# 01_digital_back_end.net
KiCad netlist of a schematic drawn in Altium Designer
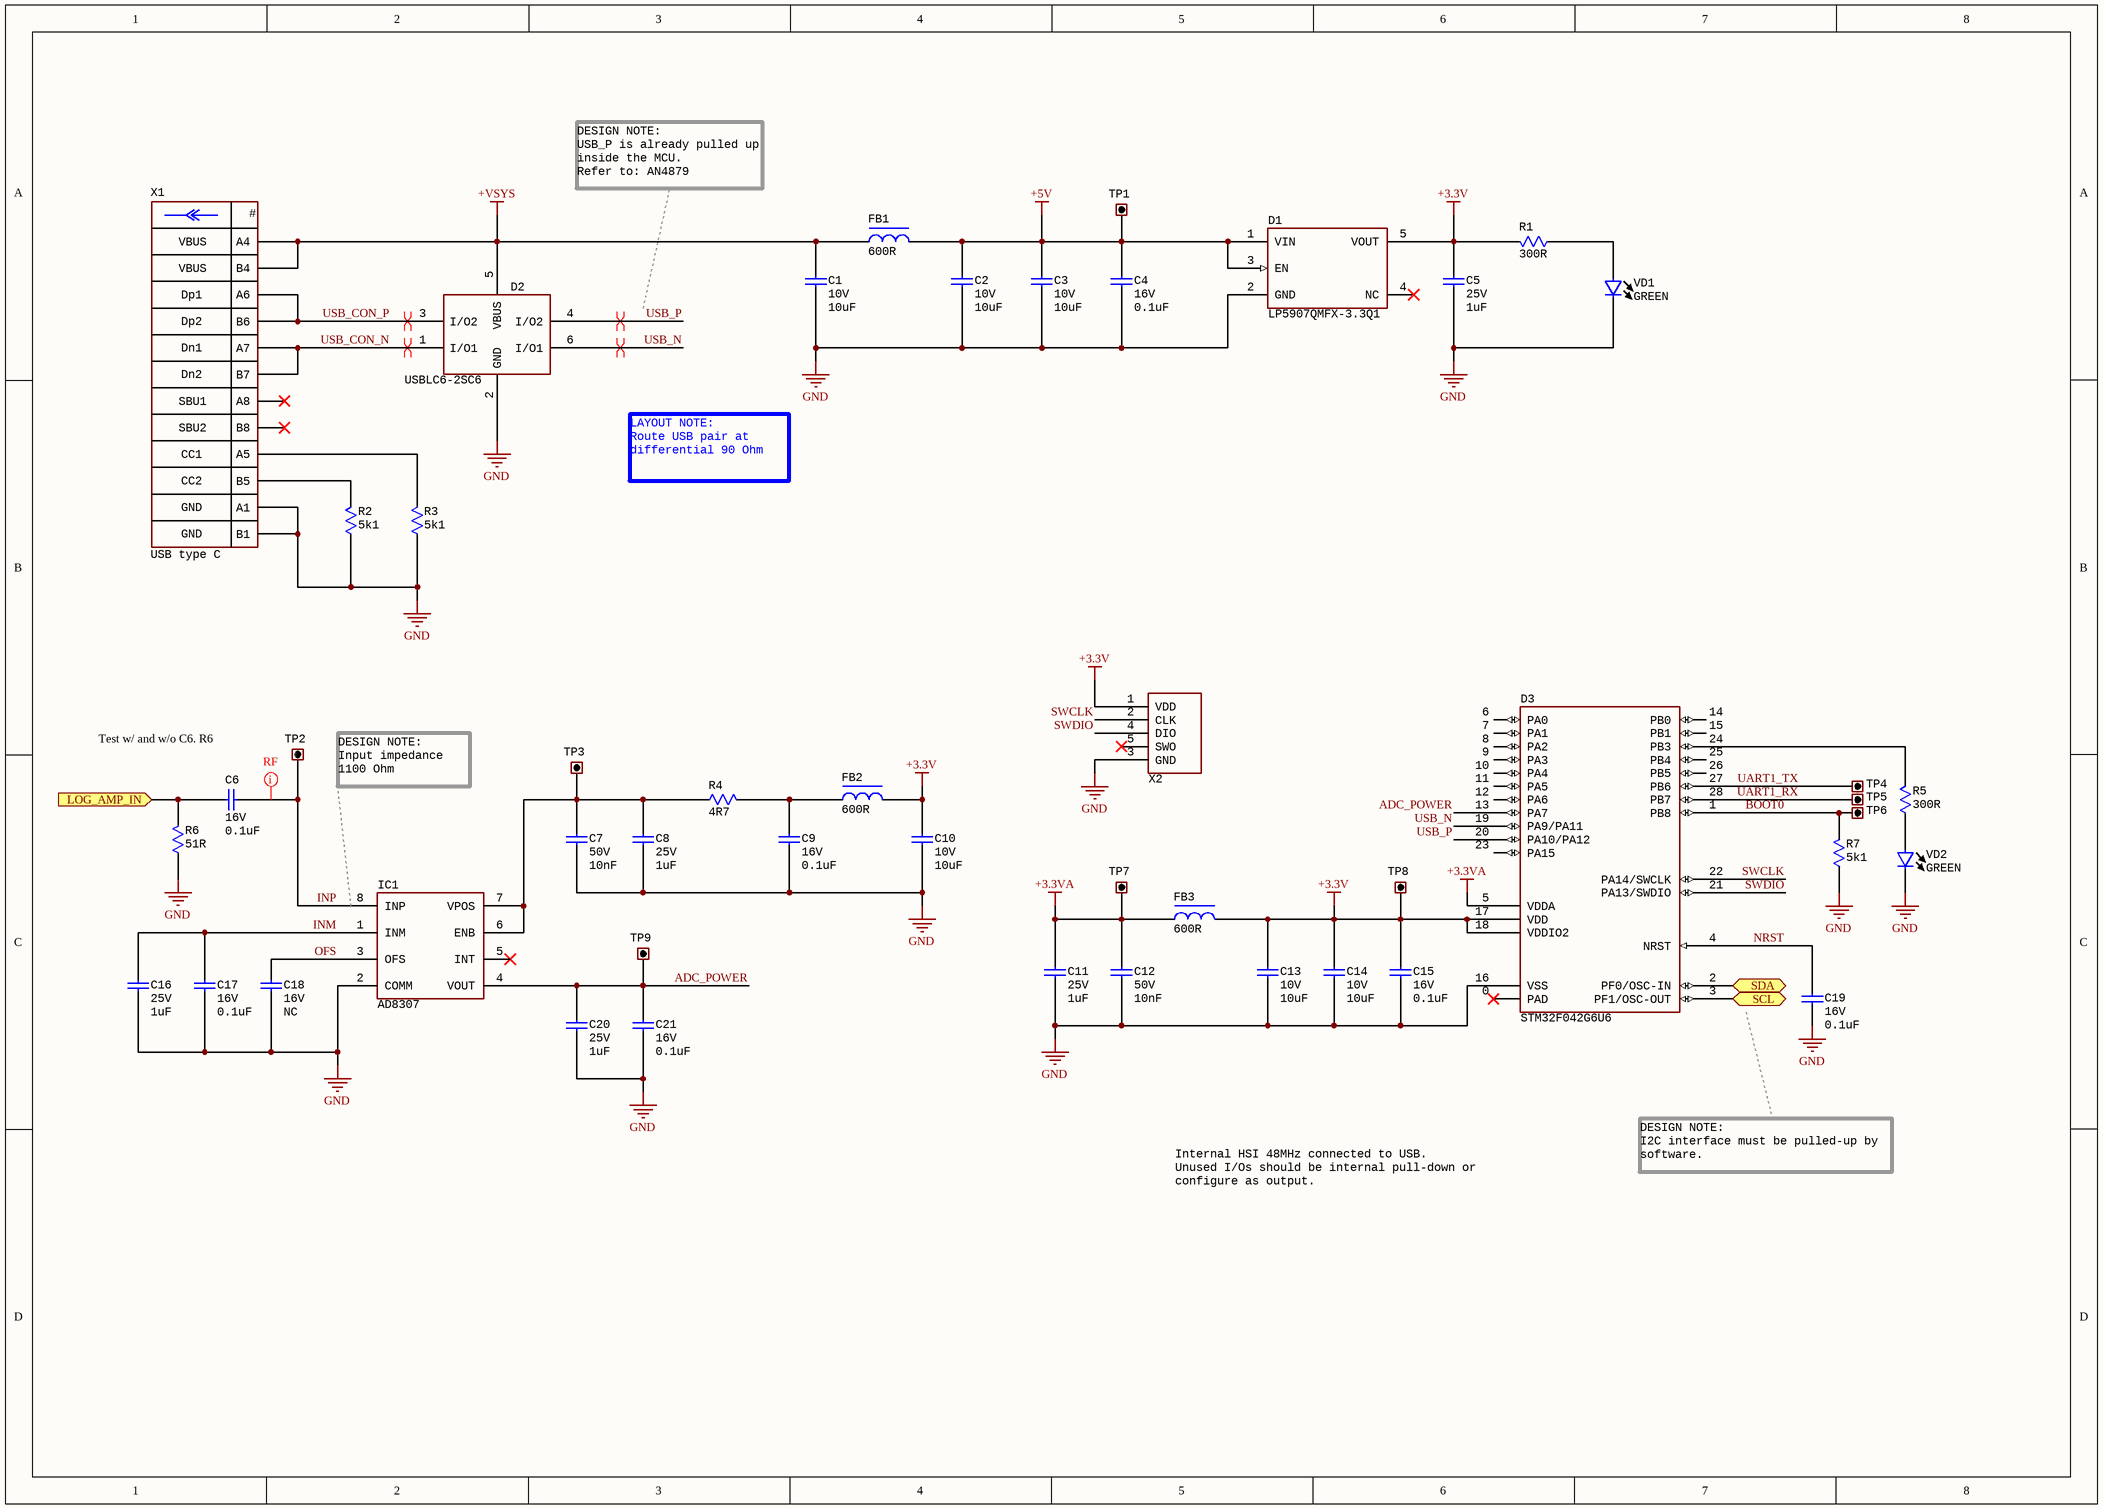
[diagram p0: 01_digital_back_end.SchDoc]

(export (version "E")
  (design (tool "Eeschema 10.0.6"))
  (components
    (comp (ref "C1")
      (value "10uF")
      (footprint "standard-case:CAP: 0603")
      (fields
        (field (name "MANUFACTURER") "Samsung Electro-Mechanics")
        (field (name "PARTNUMBER") "CL10A106KP8NNNC")
        (field (name "VALUEMANUFACTURERPARTNUMBER") "Ceramic capacitor, 10uF, X5R, ±10%, 10V, 0603, -55...+125°C")
        (field (name "VOLTAGE") "10V")
      )
      (libsource (lib "Schlib") (part "Ceramic"))
    )
    (comp (ref "C2")
      (value "10uF")
      (footprint "standard-case:CAP: 0603")
      (fields
        (field (name "MANUFACTURER") "Samsung Electro-Mechanics")
        (field (name "PARTNUMBER") "CL10A106KP8NNNC")
        (field (name "VALUEMANUFACTURERPARTNUMBER") "Ceramic capacitor, 10uF, X5R, ±10%, 10V, 0603, -55...+125°C")
        (field (name "VOLTAGE") "10V")
      )
      (libsource (lib "Schlib") (part "Ceramic"))
    )
    (comp (ref "C3")
      (value "10uF")
      (footprint "standard-case:CAP: 0603")
      (fields
        (field (name "MANUFACTURER") "Samsung Electro-Mechanics")
        (field (name "PARTNUMBER") "CL10A106KP8NNNC")
        (field (name "VALUEMANUFACTURERPARTNUMBER") "Ceramic capacitor, 10uF, X5R, ±10%, 10V, 0603, -55...+125°C")
        (field (name "VOLTAGE") "10V")
      )
      (libsource (lib "Schlib") (part "Ceramic"))
    )
    (comp (ref "C4")
      (value "0.1uF")
      (footprint "standard-case:CAP: 0402")
      (fields
        (field (name "MANUFACTURER") "Samsung Electro-Mechanics")
        (field (name "PARTNUMBER") "CL05B104KO5NNNC")
        (field (name "VALUEMANUFACTURERPARTNUMBER") "Ceramic capacitor, 0.1uF, X7R, ±10%, 16V, 0402, -55...+125°C")
        (field (name "VOLTAGE") "16V")
      )
      (libsource (lib "Schlib") (part "Ceramic"))
    )
    (comp (ref "C5")
      (value "1uF")
      (footprint "standard-case:CAP: 0402")
      (fields
        (field (name "MANUFACTURER") "Samsung Electro-Mechanics")
        (field (name "PARTNUMBER") "CL05A105KA5NQNC")
        (field (name "VALUEMANUFACTURERPARTNUMBER") "Ceramic capacitor, 1uF, X5R, ±10%, 25V, 0402, -55...+125°C")
        (field (name "VOLTAGE") "25V")
      )
      (libsource (lib "Schlib") (part "Ceramic"))
    )
    (comp (ref "C6")
      (value "0.1uF")
      (footprint "standard-case:CAP: 0402")
      (fields
        (field (name "MANUFACTURER") "Samsung Electro-Mechanics")
        (field (name "PARTNUMBER") "CL05B104KO5NNNC")
        (field (name "VALUEMANUFACTURERPARTNUMBER") "Ceramic capacitor, 0.1uF, X7R, ±10%, 16V, 0402, -55...+125°C")
        (field (name "VOLTAGE") "16V")
      )
      (libsource (lib "Schlib") (part "Ceramic"))
    )
    (comp (ref "C7")
      (value "10nF")
      (footprint "standard-case:CAP: 0402")
      (fields
        (field (name "MANUFACTURER") "Samsung Electro-Mechanics")
        (field (name "PARTNUMBER") "CL05B103KB5NNNC")
        (field (name "VALUEMANUFACTURERPARTNUMBER") "Ceramic capacitor, 10nF, X7R, ±10%, 50V, 0402, -55...+125°C")
        (field (name "VOLTAGE") "50V")
      )
      (libsource (lib "Schlib") (part "Ceramic"))
    )
    (comp (ref "C8")
      (value "1uF")
      (footprint "standard-case:CAP: 0402")
      (fields
        (field (name "MANUFACTURER") "Samsung Electro-Mechanics")
        (field (name "PARTNUMBER") "CL05A105KA5NQNC")
        (field (name "VALUEMANUFACTURERPARTNUMBER") "Ceramic capacitor, 1uF, X5R, ±10%, 25V, 0402, -55...+125°C")
        (field (name "VOLTAGE") "25V")
      )
      (libsource (lib "Schlib") (part "Ceramic"))
    )
    (comp (ref "C9")
      (value "0.1uF")
      (footprint "standard-case:CAP: 0402")
      (fields
        (field (name "MANUFACTURER") "Samsung Electro-Mechanics")
        (field (name "PARTNUMBER") "CL05B104KO5NNNC")
        (field (name "VALUEMANUFACTURERPARTNUMBER") "Ceramic capacitor, 0.1uF, X7R, ±10%, 16V, 0402, -55...+125°C")
        (field (name "VOLTAGE") "16V")
      )
      (libsource (lib "Schlib") (part "Ceramic"))
    )
    (comp (ref "C10")
      (value "10uF")
      (footprint "standard-case:CAP: 0603")
      (fields
        (field (name "MANUFACTURER") "Samsung Electro-Mechanics")
        (field (name "PARTNUMBER") "CL10A106KP8NNNC")
        (field (name "VALUEMANUFACTURERPARTNUMBER") "Ceramic capacitor, 10uF, X5R, ±10%, 10V, 0603, -55...+125°C")
        (field (name "VOLTAGE") "10V")
      )
      (libsource (lib "Schlib") (part "Ceramic"))
    )
    (comp (ref "C11")
      (value "1uF")
      (footprint "standard-case:CAP: 0402")
      (fields
        (field (name "MANUFACTURER") "Samsung Electro-Mechanics")
        (field (name "PARTNUMBER") "CL05A105KA5NQNC")
        (field (name "VALUEMANUFACTURERPARTNUMBER") "Ceramic capacitor, 1uF, X5R, ±10%, 25V, 0402, -55...+125°C")
        (field (name "VOLTAGE") "25V")
      )
      (libsource (lib "Schlib") (part "Ceramic"))
    )
    (comp (ref "C12")
      (value "10nF")
      (footprint "standard-case:CAP: 0402")
      (fields
        (field (name "MANUFACTURER") "Samsung Electro-Mechanics")
        (field (name "PARTNUMBER") "CL05B103KB5NNNC")
        (field (name "VALUEMANUFACTURERPARTNUMBER") "Ceramic capacitor, 10nF, X7R, ±10%, 50V, 0402, -55...+125°C")
        (field (name "VOLTAGE") "50V")
      )
      (libsource (lib "Schlib") (part "Ceramic"))
    )
    (comp (ref "C13")
      (value "10uF")
      (footprint "standard-case:CAP: 0603")
      (fields
        (field (name "MANUFACTURER") "Samsung Electro-Mechanics")
        (field (name "PARTNUMBER") "CL10A106KP8NNNC")
        (field (name "VALUEMANUFACTURERPARTNUMBER") "Ceramic capacitor, 10uF, X5R, ±10%, 10V, 0603, -55...+125°C")
        (field (name "VOLTAGE") "10V")
      )
      (libsource (lib "Schlib") (part "Ceramic"))
    )
    (comp (ref "C14")
      (value "10uF")
      (footprint "standard-case:CAP: 0603")
      (fields
        (field (name "MANUFACTURER") "Samsung Electro-Mechanics")
        (field (name "PARTNUMBER") "CL10A106KP8NNNC")
        (field (name "VALUEMANUFACTURERPARTNUMBER") "Ceramic capacitor, 10uF, X5R, ±10%, 10V, 0603, -55...+125°C")
        (field (name "VOLTAGE") "10V")
      )
      (libsource (lib "Schlib") (part "Ceramic"))
    )
    (comp (ref "C15")
      (value "0.1uF")
      (footprint "standard-case:CAP: 0402")
      (fields
        (field (name "MANUFACTURER") "Samsung Electro-Mechanics")
        (field (name "PARTNUMBER") "CL05B104KO5NNNC")
        (field (name "VALUEMANUFACTURERPARTNUMBER") "Ceramic capacitor, 0.1uF, X7R, ±10%, 16V, 0402, -55...+125°C")
        (field (name "VOLTAGE") "16V")
      )
      (libsource (lib "Schlib") (part "Ceramic"))
    )
    (comp (ref "C16")
      (value "1uF")
      (footprint "standard-case:CAP: 0402")
      (fields
        (field (name "MANUFACTURER") "Samsung Electro-Mechanics")
        (field (name "PARTNUMBER") "CL05A105KA5NQNC")
        (field (name "VALUEMANUFACTURERPARTNUMBER") "Ceramic capacitor, 1uF, X5R, ±10%, 25V, 0402, -55...+125°C")
        (field (name "VOLTAGE") "25V")
      )
      (libsource (lib "Schlib") (part "Ceramic"))
    )
    (comp (ref "C17")
      (value "0.1uF")
      (footprint "standard-case:CAP: 0402")
      (fields
        (field (name "MANUFACTURER") "Samsung Electro-Mechanics")
        (field (name "PARTNUMBER") "CL05B104KO5NNNC")
        (field (name "VALUEMANUFACTURERPARTNUMBER") "Ceramic capacitor, 0.1uF, X7R, ±10%, 16V, 0402, -55...+125°C")
        (field (name "VOLTAGE") "16V")
      )
      (libsource (lib "Schlib") (part "Ceramic"))
    )
    (comp (ref "C18")
      (value "NC")
      (footprint "standard-case:CAP: 0402")
      (fields
        (field (name "MANUFACTURER") "Yageo")
        (field (name "PARTNUMBER") "CC0201KRX7R7BB103")
        (field (name "VALUEMANUFACTURERPARTNUMBER") "Ceramic capacitor, NC, X7R, ±10%, 16V, 0603, -55...+125°C")
        (field (name "VOLTAGE") "16V")
      )
      (libsource (lib "Schlib") (part "Ceramic"))
    )
    (comp (ref "C19")
      (value "0.1uF")
      (footprint "standard-case:CAP: 0402")
      (fields
        (field (name "MANUFACTURER") "Samsung Electro-Mechanics")
        (field (name "PARTNUMBER") "CL05B104KO5NNNC")
        (field (name "VALUEMANUFACTURERPARTNUMBER") "Ceramic capacitor, 0.1uF, X7R, ±10%, 16V, 0402, -55...+125°C")
        (field (name "VOLTAGE") "16V")
      )
      (libsource (lib "Schlib") (part "Ceramic"))
    )
    (comp (ref "C20")
      (value "1uF")
      (footprint "standard-case:CAP: 0402")
      (fields
        (field (name "MANUFACTURER") "Samsung Electro-Mechanics")
        (field (name "PARTNUMBER") "CL05A105KA5NQNC")
        (field (name "VALUEMANUFACTURERPARTNUMBER") "Ceramic capacitor, 1uF, X5R, ±10%, 25V, 0402, -55...+125°C")
        (field (name "VOLTAGE") "25V")
      )
      (libsource (lib "Schlib") (part "Ceramic"))
    )
    (comp (ref "C21")
      (value "0.1uF")
      (footprint "standard-case:CAP: 0402")
      (fields
        (field (name "MANUFACTURER") "Samsung Electro-Mechanics")
        (field (name "PARTNUMBER") "CL05B104KO5NNNC")
        (field (name "VALUEMANUFACTURERPARTNUMBER") "Ceramic capacitor, 0.1uF, X7R, ±10%, 16V, 0402, -55...+125°C")
        (field (name "VOLTAGE") "16V")
      )
      (libsource (lib "Schlib") (part "Ceramic"))
    )
    (comp (ref "D1") (value "LP5907QMFX-3.3Q1") (footprint "SOT23-5") (libsource (lib "Schlib") (part "LDO")))
    (comp (ref "D2")
      (value "~")
      (footprint "standard-case:SOT23-6")
      (fields
        (field (name "MANUFACTURER") "STMicroelectronics")
        (field (name "VALUEMANUFACTURERPARTNUMBER") "USB protection, , 5A peak, 17V, Power line, SOT-23-6, -40...+125°C")
        (field (name "PARTNUMBER") "USBLC6-2SC6")
      )
      (libsource (lib "Schlib") (part "USBLC6-2SC6"))
    )
    (comp (ref "D3")
      (value "STM32F042G6U6")
      (footprint "28-QFN (4x4)")
      (description "Cortex-M0, 48MHz, 32KB ROM, 6KB RAM, 2.4...3.6V, QFN-28, -40...+85°C")
      (fields
        (field (name "MANUFACTURER") "STMicroelectronics")
        (field (name "PARTNUMBER") "STM32F042G6U6")
        (field (name "JLCPCB PART #") "C961597")
      )
      (libsource (lib "Schlib") (part "STM32F042G6U6"))
    )
    (comp (ref "FB1")
      (value "~")
      (footprint "standard-case:IND: 0603")
      (fields
        (field (name "MANUFACTURER") "Sunlord")
        (field (name "PARTNUMBER") "LQP03TNR10J02D")
        (field (name "VALUEMANUFACTURERPARTNUMBER") "Ferrite Bead, , , 0603, 200mA, -55...+125°C")
        (field (name "RESISTANCE") "600R")
      )
      (libsource (lib "Schlib") (part "Ferrite_Bead_SMD"))
    )
    (comp (ref "FB2")
      (value "~")
      (footprint "standard-case:IND: 0603")
      (fields
        (field (name "MANUFACTURER") "Sunlord")
        (field (name "PARTNUMBER") "LQP03TNR10J02D")
        (field (name "VALUEMANUFACTURERPARTNUMBER") "Ferrite Bead, , , 0603, 200mA, -55...+125°C")
        (field (name "RESISTANCE") "600R")
      )
      (libsource (lib "Schlib") (part "Ferrite_Bead_SMD"))
    )
    (comp (ref "FB3")
      (value "~")
      (footprint "standard-case:IND: 0603")
      (fields
        (field (name "MANUFACTURER") "Sunlord")
        (field (name "PARTNUMBER") "LQP03TNR10J02D")
        (field (name "VALUEMANUFACTURERPARTNUMBER") "Ferrite Bead, , , 0603, 200mA, -55...+125°C")
        (field (name "RESISTANCE") "600R")
      )
      (libsource (lib "Schlib") (part "Ferrite_Bead_SMD"))
    )
    (comp (ref "IC1")
      (value "AD8307")
      (footprint "8-SOIC")
      (description "Integrated Circuit")
      (libsource (lib "Schlib") (part "AD8307"))
    )
    (comp (ref "R1")
      (value "300R")
      (footprint "standard-case:RES: 0603")
      (fields
        (field (name "MANUFACTURER") "Yageo")
        (field (name "PARTNUMBER") "RC0201JR-07100RL")
        (field (name "VALUEMANUFACTURERPARTNUMBER") "Resistor film, 300R, ±5%, 0603, 0.05W, -55...+125°C")
      )
      (libsource (lib "Schlib") (part "Resistor"))
    )
    (comp (ref "R2")
      (value "5k1")
      (footprint "standard-case:RES: 0603")
      (fields
        (field (name "MANUFACTURER") "Yageo")
        (field (name "PARTNUMBER") "0603WAF5101T5E")
        (field (name "VALUEMANUFACTURERPARTNUMBER") "Resistor film, 5k1, ±5%, 0603, 0.05W, -55...+125°C")
      )
      (libsource (lib "Schlib") (part "Resistor"))
    )
    (comp (ref "R3")
      (value "5k1")
      (footprint "standard-case:RES: 0603")
      (fields
        (field (name "MANUFACTURER") "Yageo")
        (field (name "PARTNUMBER") "0603WAF5101T5E")
        (field (name "VALUEMANUFACTURERPARTNUMBER") "Resistor film, 5k1, ±5%, 0603, 0.05W, -55...+125°C")
      )
      (libsource (lib "Schlib") (part "Resistor"))
    )
    (comp (ref "R4")
      (value "4R7")
      (footprint "standard-case:RES: 0603")
      (fields
        (field (name "MANUFACTURER") "Yageo")
        (field (name "PARTNUMBER") "RC0201JR-07100RL")
        (field (name "VALUEMANUFACTURERPARTNUMBER") "Resistor film, 4R7, ±5%, 0603, 0.05W, -55...+125°C")
      )
      (libsource (lib "Schlib") (part "Resistor"))
    )
    (comp (ref "R5")
      (value "300R")
      (footprint "standard-case:RES: 0603")
      (fields
        (field (name "MANUFACTURER") "Yageo")
        (field (name "PARTNUMBER") "RC0201JR-07100RL")
        (field (name "VALUEMANUFACTURERPARTNUMBER") "Resistor film, 300R, ±5%, 0603, 0.05W, -55...+125°C")
      )
      (libsource (lib "Schlib") (part "Resistor"))
    )
    (comp (ref "R6")
      (value "51R")
      (footprint "standard-case:RES: 0603")
      (fields
        (field (name "MANUFACTURER") "Yageo")
        (field (name "PARTNUMBER") "0603WAF5101T5E")
        (field (name "VALUEMANUFACTURERPARTNUMBER") "Resistor film, 51R, ±5%, 0603, 0.05W, -55...+125°C")
      )
      (libsource (lib "Schlib") (part "Resistor"))
    )
    (comp (ref "R7")
      (value "5k1")
      (footprint "standard-case:RES: 0603")
      (fields
        (field (name "MANUFACTURER") "Yageo")
        (field (name "PARTNUMBER") "RC0201JR-07100RL")
        (field (name "VALUEMANUFACTURERPARTNUMBER") "Resistor film, 5k1, ±5%, 0603, 0.05W, -55...+125°C")
      )
      (libsource (lib "Schlib") (part "Resistor"))
    )
    (comp (ref "TP1")
      (value "~")
      (footprint "CON: test_point")
      (fields
        (field (name "MANUFACTURER") "Keystone")
        (field (name "VALUEMANUFACTURERPARTNUMBER") "Test point, Keystone, 5001")
        (field (name "PARTNUMBER") "5001")
      )
      (libsource (lib "") (part "Connector_Test_Point_1"))
    )
    (comp (ref "TP2")
      (value "~")
      (footprint "CON: test_point")
      (fields
        (field (name "MANUFACTURER") "Keystone")
        (field (name "VALUEMANUFACTURERPARTNUMBER") "Test point, Keystone, 5001")
        (field (name "PARTNUMBER") "5001")
      )
      (libsource (lib "") (part "Connector_Test_Point_1"))
    )
    (comp (ref "TP3")
      (value "~")
      (footprint "CON: test_point")
      (fields
        (field (name "MANUFACTURER") "Keystone")
        (field (name "VALUEMANUFACTURERPARTNUMBER") "Test point, Keystone, 5001")
        (field (name "PARTNUMBER") "5001")
      )
      (libsource (lib "") (part "Connector_Test_Point_1"))
    )
    (comp (ref "TP4")
      (value "~")
      (footprint "CON: test_point")
      (fields
        (field (name "MANUFACTURER") "Keystone")
        (field (name "VALUEMANUFACTURERPARTNUMBER") "Test point, Keystone, 5001")
        (field (name "PARTNUMBER") "5001")
      )
      (libsource (lib "Schlib") (part "Connector_Test_Point"))
    )
    (comp (ref "TP5")
      (value "~")
      (footprint "CON: test_point")
      (fields
        (field (name "MANUFACTURER") "Keystone")
        (field (name "VALUEMANUFACTURERPARTNUMBER") "Test point, Keystone, 5001")
        (field (name "PARTNUMBER") "5001")
      )
      (libsource (lib "Schlib") (part "Connector_Test_Point"))
    )
    (comp (ref "TP6")
      (value "~")
      (footprint "CON: test_point")
      (fields
        (field (name "MANUFACTURER") "Keystone")
        (field (name "VALUEMANUFACTURERPARTNUMBER") "Test point, Keystone, 5001")
        (field (name "PARTNUMBER") "5001")
      )
      (libsource (lib "Schlib") (part "Connector_Test_Point"))
    )
    (comp (ref "TP7")
      (value "~")
      (footprint "CON: test_point")
      (fields
        (field (name "MANUFACTURER") "Keystone")
        (field (name "VALUEMANUFACTURERPARTNUMBER") "Test point, Keystone, 5001")
        (field (name "PARTNUMBER") "5001")
      )
      (libsource (lib "") (part "Connector_Test_Point_1"))
    )
    (comp (ref "TP8")
      (value "~")
      (footprint "CON: test_point")
      (fields
        (field (name "MANUFACTURER") "Keystone")
        (field (name "VALUEMANUFACTURERPARTNUMBER") "Test point, Keystone, 5001")
        (field (name "PARTNUMBER") "5001")
      )
      (libsource (lib "") (part "Connector_Test_Point_1"))
    )
    (comp (ref "TP9")
      (value "~")
      (footprint "CON: test_point")
      (fields
        (field (name "MANUFACTURER") "Keystone")
        (field (name "VALUEMANUFACTURERPARTNUMBER") "Test point, Keystone, 5001")
        (field (name "PARTNUMBER") "5001")
      )
      (libsource (lib "") (part "Connector_Test_Point_1"))
    )
    (comp (ref "VD1")
      (value "~")
      (footprint "standard-case:LED: 0603B")
      (fields
        (field (name "VALUEMANUFACTURERPARTNUMBER") "LED, Green, *, *, *, -55...+150°C")
        (field (name "COLOR") "GREEN")
        (field (name "JLCPCB PART #") "C72041")
      )
      (libsource (lib "Schlib") (part "LED_single"))
    )
    (comp (ref "VD2")
      (value "~")
      (footprint "standard-case:LED: 0603B")
      (fields
        (field (name "VALUEMANUFACTURERPARTNUMBER") "LED, Green, *, *, *, -55...+150°C")
        (field (name "COLOR") "GREEN")
        (field (name "JLCPCB PART #") "C72041")
      )
      (libsource (lib "Schlib") (part "LED_single"))
    )
    (comp (ref "X1")
      (value "~")
      (footprint "custom-case:CON: TYPE-C-31-M-12")
      (fields
        (field (name "MANUFACTURER") "Korean Hroparts")
        (field (name "VALUEMANUFACTURERPARTNUMBER") "USB Type C, 3A")
        (field (name "PARTNUMBER") "TYPE-C-31-M-12")
        (field (name "COMMENTTEXT") "USB type C")
      )
      (libsource (lib "Schlib") (part "Connector_USB_Type_C"))
    )
    (comp (ref "X2")
      (value "~")
      (footprint "CON: 1.27 Pogo Pin contact")
      (description "SWD Interface")
      (libsource (lib "Schlib") (part "Connector SWD"))
    )
  )
  (nets
    (net (code "1") (name "+3.3V") (class "Default")
      (node (ref "C10") (pin "1") (pinfunction "1_1") (pintype "passive"))
      (node (ref "C13") (pin "1") (pinfunction "1_1") (pintype "passive"))
      (node (ref "C14") (pin "1") (pinfunction "1_1") (pintype "passive"))
      (node (ref "C15") (pin "1") (pinfunction "1_1") (pintype "passive"))
      (node (ref "C5") (pin "1") (pinfunction "1_1") (pintype "passive"))
      (node (ref "D1") (pin "5") (pinfunction "VOUT_5") (pintype "power_in"))
      (node (ref "D3") (pin "17") (pinfunction "VDD_17") (pintype "passive"))
      (node (ref "D3") (pin "18") (pinfunction "VDDIO2_18") (pintype "passive"))
      (node (ref "FB2") (pin "1") (pinfunction "1_1") (pintype "passive"))
      (node (ref "FB3") (pin "1") (pinfunction "1_1") (pintype "passive"))
      (node (ref "R1") (pin "2") (pinfunction "2_2") (pintype "passive"))
      (node (ref "TP8") (pin "1") (pinfunction "1_1") (pintype "passive"))
      (node (ref "X2") (pin "1") (pinfunction "VDD_1") (pintype "passive"))
    )
    (net (code "2") (name "+3.3VA") (class "Default")
      (node (ref "C11") (pin "1") (pinfunction "1_1") (pintype "passive"))
      (node (ref "C12") (pin "1") (pinfunction "1_1") (pintype "passive"))
      (node (ref "D3") (pin "5") (pinfunction "VDDA_5") (pintype "passive"))
      (node (ref "FB3") (pin "2") (pinfunction "2_2") (pintype "passive"))
      (node (ref "TP7") (pin "1") (pinfunction "1_1") (pintype "passive"))
    )
    (net (code "3") (name "+5V") (class "Default")
      (node (ref "C2") (pin "1") (pinfunction "1_1") (pintype "passive"))
      (node (ref "C3") (pin "1") (pinfunction "1_1") (pintype "passive"))
      (node (ref "C4") (pin "1") (pinfunction "1_1") (pintype "passive"))
      (node (ref "D1") (pin "1") (pinfunction "VIN_1") (pintype "power_in"))
      (node (ref "D1") (pin "3") (pinfunction "EN_3") (pintype "input"))
      (node (ref "FB1") (pin "1") (pinfunction "1_1") (pintype "passive"))
      (node (ref "TP1") (pin "1") (pinfunction "1_1") (pintype "passive"))
    )
    (net (code "4") (name "+VSYS") (class "Default")
      (node (ref "C1") (pin "1") (pinfunction "1_1") (pintype "passive"))
      (node (ref "D2") (pin "5") (pinfunction "VBUS_5") (pintype "passive"))
      (node (ref "FB1") (pin "2") (pinfunction "2_2") (pintype "passive"))
      (node (ref "X1") (pin "A4") (pinfunction "A4_A4") (pintype "passive"))
      (node (ref "X1") (pin "B4") (pinfunction "B4_B4") (pintype "passive"))
    )
    (net (code "5") (name "/ADC_POWER") (class "Default")
      (node (ref "C20") (pin "1") (pinfunction "1_1") (pintype "passive"))
      (node (ref "C21") (pin "1") (pinfunction "1_1") (pintype "passive"))
      (node (ref "D3") (pin "13") (pinfunction "PA7_13") (pintype "bidirectional"))
      (node (ref "IC1") (pin "4") (pinfunction "VOUT_4") (pintype "passive"))
      (node (ref "TP9") (pin "1") (pinfunction "1_1") (pintype "passive"))
    )
    (net (code "6") (name "/BOOT0") (class "Default")
      (node (ref "D3") (pin "1") (pinfunction "PB8_1") (pintype "bidirectional"))
      (node (ref "R7") (pin "2") (pinfunction "2_2") (pintype "passive"))
      (node (ref "TP6") (pin "1") (pinfunction "1_1") (pintype "passive"))
    )
    (net (code "7") (name "/INM") (class "Default")
      (node (ref "C16") (pin "1") (pinfunction "1_1") (pintype "passive"))
      (node (ref "C17") (pin "1") (pinfunction "1_1") (pintype "passive"))
      (node (ref "IC1") (pin "1") (pinfunction "INM_1") (pintype "passive"))
    )
    (net (code "8") (name "/INP") (class "Default")
      (node (ref "C6") (pin "2") (pinfunction "2_2") (pintype "passive"))
      (node (ref "IC1") (pin "8") (pinfunction "INP_8") (pintype "passive"))
      (node (ref "TP2") (pin "1") (pinfunction "1_1") (pintype "passive"))
    )
    (net (code "9") (name "/LOG_AMP_IN") (class "Default")
      (node (ref "C6") (pin "1") (pinfunction "1_1") (pintype "passive"))
      (node (ref "R6") (pin "2") (pinfunction "2_2") (pintype "passive"))
    )
    (net (code "10") (name "/NRST") (class "Default")
      (node (ref "C19") (pin "1") (pinfunction "1_1") (pintype "passive"))
      (node (ref "D3") (pin "4") (pinfunction "NRST_4") (pintype "input"))
    )
    (net (code "11") (name "/OFS") (class "Default")
      (node (ref "C18") (pin "1") (pinfunction "1_1") (pintype "passive"))
      (node (ref "IC1") (pin "3") (pinfunction "OFS_3") (pintype "passive"))
    )
    (net (code "12") (name "/SCL") (class "Default")
      (node (ref "D3") (pin "3") (pinfunction "PF1/OSC-OUT_3") (pintype "bidirectional"))
    )
    (net (code "13") (name "/SDA") (class "Default")
      (node (ref "D3") (pin "2") (pinfunction "PF0/OSC-IN_2") (pintype "bidirectional"))
    )
    (net (code "14") (name "/SWCLK") (class "Default")
      (node (ref "D3") (pin "22") (pinfunction "PA14/SWCLK_22") (pintype "bidirectional"))
      (node (ref "X2") (pin "2") (pinfunction "CLK_2") (pintype "passive"))
    )
    (net (code "15") (name "/SWDIO") (class "Default")
      (node (ref "D3") (pin "21") (pinfunction "PA13/SWDIO_21") (pintype "bidirectional"))
      (node (ref "X2") (pin "4") (pinfunction "DIO_4") (pintype "passive"))
    )
    (net (code "16") (name "/UART1_RX") (class "Default")
      (node (ref "D3") (pin "28") (pinfunction "PB7_28") (pintype "bidirectional"))
      (node (ref "TP5") (pin "1") (pinfunction "1_1") (pintype "passive"))
    )
    (net (code "17") (name "/UART1_TX") (class "Default")
      (node (ref "D3") (pin "27") (pinfunction "PB6_27") (pintype "bidirectional"))
      (node (ref "TP4") (pin "1") (pinfunction "1_1") (pintype "passive"))
    )
    (net (code "18") (name "/USB_CON_N") (class "Default")
      (node (ref "D2") (pin "1") (pinfunction "I/O1_1") (pintype "passive"))
      (node (ref "X1") (pin "A7") (pinfunction "A7_A7") (pintype "passive"))
      (node (ref "X1") (pin "B7") (pinfunction "B7_B7") (pintype "passive"))
    )
    (net (code "19") (name "/USB_CON_P") (class "Default")
      (node (ref "D2") (pin "3") (pinfunction "I/O2_3") (pintype "passive"))
      (node (ref "X1") (pin "A6") (pinfunction "A6_A6") (pintype "passive"))
      (node (ref "X1") (pin "B6") (pinfunction "B6_B6") (pintype "passive"))
    )
    (net (code "20") (name "/USB_N") (class "Default")
      (node (ref "D2") (pin "6") (pinfunction "I/O1_6") (pintype "passive"))
      (node (ref "D3") (pin "19") (pinfunction "PA9/PA11_19") (pintype "bidirectional"))
    )
    (net (code "21") (name "/USB_P") (class "Default")
      (node (ref "D2") (pin "4") (pinfunction "I/O2_4") (pintype "passive"))
      (node (ref "D3") (pin "20") (pinfunction "PA10/PA12_20") (pintype "bidirectional"))
    )
    (net (code "22") (name "GND") (class "Default")
      (node (ref "C1") (pin "2") (pinfunction "2_2") (pintype "passive"))
      (node (ref "C10") (pin "2") (pinfunction "2_2") (pintype "passive"))
      (node (ref "C11") (pin "2") (pinfunction "2_2") (pintype "passive"))
      (node (ref "C12") (pin "2") (pinfunction "2_2") (pintype "passive"))
      (node (ref "C13") (pin "2") (pinfunction "2_2") (pintype "passive"))
      (node (ref "C14") (pin "2") (pinfunction "2_2") (pintype "passive"))
      (node (ref "C15") (pin "2") (pinfunction "2_2") (pintype "passive"))
      (node (ref "C16") (pin "2") (pinfunction "2_2") (pintype "passive"))
      (node (ref "C17") (pin "2") (pinfunction "2_2") (pintype "passive"))
      (node (ref "C18") (pin "2") (pinfunction "2_2") (pintype "passive"))
      (node (ref "C19") (pin "2") (pinfunction "2_2") (pintype "passive"))
      (node (ref "C2") (pin "2") (pinfunction "2_2") (pintype "passive"))
      (node (ref "C20") (pin "2") (pinfunction "2_2") (pintype "passive"))
      (node (ref "C21") (pin "2") (pinfunction "2_2") (pintype "passive"))
      (node (ref "C3") (pin "2") (pinfunction "2_2") (pintype "passive"))
      (node (ref "C4") (pin "2") (pinfunction "2_2") (pintype "passive"))
      (node (ref "C5") (pin "2") (pinfunction "2_2") (pintype "passive"))
      (node (ref "C7") (pin "2") (pinfunction "2_2") (pintype "passive"))
      (node (ref "C8") (pin "2") (pinfunction "2_2") (pintype "passive"))
      (node (ref "C9") (pin "2") (pinfunction "2_2") (pintype "passive"))
      (node (ref "D1") (pin "2") (pinfunction "GND_2") (pintype "passive"))
      (node (ref "D2") (pin "2") (pinfunction "GND_2") (pintype "passive"))
      (node (ref "D3") (pin "16") (pinfunction "VSS_16") (pintype "passive"))
      (node (ref "IC1") (pin "2") (pinfunction "COMM_2") (pintype "passive"))
      (node (ref "R2") (pin "1") (pinfunction "1_1") (pintype "passive"))
      (node (ref "R3") (pin "1") (pinfunction "1_1") (pintype "passive"))
      (node (ref "R6") (pin "1") (pinfunction "1_1") (pintype "passive"))
      (node (ref "R7") (pin "1") (pinfunction "1_1") (pintype "passive"))
      (node (ref "VD1") (pin "2") (pinfunction "2_2") (pintype "passive"))
      (node (ref "VD2") (pin "2") (pinfunction "2_2") (pintype "passive"))
      (node (ref "X1") (pin "A1") (pinfunction "A1_A1") (pintype "passive"))
      (node (ref "X1") (pin "B1") (pinfunction "B1_B1") (pintype "passive"))
      (node (ref "X2") (pin "3") (pinfunction "GND_3") (pintype "passive"))
    )
    (net (code "23") (name "Net-(C9-Pad1)") (class "Default")
      (node (ref "C9") (pin "1") (pinfunction "1_1") (pintype "passive"))
      (node (ref "FB2") (pin "2") (pinfunction "2_2") (pintype "passive"))
      (node (ref "R4") (pin "2") (pinfunction "2_2") (pintype "passive"))
    )
    (net (code "24") (name "Net-(D3-PB3)") (class "Default")
      (node (ref "D3") (pin "24") (pinfunction "PB3_24") (pintype "bidirectional"))
      (node (ref "R5") (pin "2") (pinfunction "2_2") (pintype "passive"))
    )
    (net (code "25") (name "Net-(IC1-ENB)") (class "Default")
      (node (ref "C7") (pin "1") (pinfunction "1_1") (pintype "passive"))
      (node (ref "C8") (pin "1") (pinfunction "1_1") (pintype "passive"))
      (node (ref "IC1") (pin "6") (pinfunction "ENB_6") (pintype "passive"))
      (node (ref "IC1") (pin "7") (pinfunction "VPOS_7") (pintype "passive"))
      (node (ref "R4") (pin "1") (pinfunction "1_1") (pintype "passive"))
      (node (ref "TP3") (pin "1") (pinfunction "1_1") (pintype "passive"))
    )
    (net (code "26") (name "Net-(R1-Pad1)") (class "Default")
      (node (ref "R1") (pin "1") (pinfunction "1_1") (pintype "passive"))
      (node (ref "VD1") (pin "1") (pinfunction "1_1") (pintype "passive"))
    )
    (net (code "27") (name "Net-(R2-Pad2)") (class "Default")
      (node (ref "R2") (pin "2") (pinfunction "2_2") (pintype "passive"))
      (node (ref "X1") (pin "B5") (pinfunction "B5_B5") (pintype "passive"))
    )
    (net (code "28") (name "Net-(R3-Pad2)") (class "Default")
      (node (ref "R3") (pin "2") (pinfunction "2_2") (pintype "passive"))
      (node (ref "X1") (pin "A5") (pinfunction "A5_A5") (pintype "passive"))
    )
    (net (code "29") (name "Net-(R5-Pad1)") (class "Default")
      (node (ref "R5") (pin "1") (pinfunction "1_1") (pintype "passive"))
      (node (ref "VD2") (pin "1") (pinfunction "1_1") (pintype "passive"))
    )
    (net (code "30") (name "unconnected-(D1-NC-Pad4)") (class "Default")
      (node (ref "D1") (pin "4") (pinfunction "NC_4") (pintype "passive+no_connect"))
    )
    (net (code "31") (name "unconnected-(D3-PA0-Pad6)") (class "Default")
      (node (ref "D3") (pin "6") (pinfunction "PA0_6") (pintype "bidirectional"))
    )
    (net (code "32") (name "unconnected-(D3-PA1-Pad7)") (class "Default")
      (node (ref "D3") (pin "7") (pinfunction "PA1_7") (pintype "bidirectional"))
    )
    (net (code "33") (name "unconnected-(D3-PA2-Pad8)") (class "Default")
      (node (ref "D3") (pin "8") (pinfunction "PA2_8") (pintype "bidirectional"))
    )
    (net (code "34") (name "unconnected-(D3-PA3-Pad9)") (class "Default")
      (node (ref "D3") (pin "9") (pinfunction "PA3_9") (pintype "bidirectional"))
    )
    (net (code "35") (name "unconnected-(D3-PA4-Pad10)") (class "Default")
      (node (ref "D3") (pin "10") (pinfunction "PA4_10") (pintype "bidirectional"))
    )
    (net (code "36") (name "unconnected-(D3-PA5-Pad11)") (class "Default")
      (node (ref "D3") (pin "11") (pinfunction "PA5_11") (pintype "bidirectional"))
    )
    (net (code "37") (name "unconnected-(D3-PA6-Pad12)") (class "Default")
      (node (ref "D3") (pin "12") (pinfunction "PA6_12") (pintype "bidirectional"))
    )
    (net (code "38") (name "unconnected-(D3-PA15-Pad23)") (class "Default")
      (node (ref "D3") (pin "23") (pinfunction "PA15_23") (pintype "bidirectional"))
    )
    (net (code "39") (name "unconnected-(D3-PAD-Pad0)") (class "Default")
      (node (ref "D3") (pin "0") (pinfunction "PAD_0") (pintype "passive+no_connect"))
    )
    (net (code "40") (name "unconnected-(D3-PB0-Pad14)") (class "Default")
      (node (ref "D3") (pin "14") (pinfunction "PB0_14") (pintype "bidirectional"))
    )
    (net (code "41") (name "unconnected-(D3-PB1-Pad15)") (class "Default")
      (node (ref "D3") (pin "15") (pinfunction "PB1_15") (pintype "bidirectional"))
    )
    (net (code "42") (name "unconnected-(D3-PB4-Pad25)") (class "Default")
      (node (ref "D3") (pin "25") (pinfunction "PB4_25") (pintype "bidirectional"))
    )
    (net (code "43") (name "unconnected-(D3-PB5-Pad26)") (class "Default")
      (node (ref "D3") (pin "26") (pinfunction "PB5_26") (pintype "bidirectional"))
    )
    (net (code "44") (name "unconnected-(IC1-INT-Pad5)") (class "Default")
      (node (ref "IC1") (pin "5") (pinfunction "INT_5") (pintype "passive+no_connect"))
    )
    (net (code "45") (name "unconnected-(X1-PadA8)") (class "Default")
      (node (ref "X1") (pin "A8") (pinfunction "A8_A8") (pintype "passive+no_connect"))
    )
    (net (code "46") (name "unconnected-(X1-PadB8)") (class "Default")
      (node (ref "X1") (pin "B8") (pinfunction "B8_B8") (pintype "passive+no_connect"))
    )
    (net (code "47") (name "unconnected-(X2-SWO-Pad5)") (class "Default")
      (node (ref "X2") (pin "5") (pinfunction "SWO_5") (pintype "passive+no_connect"))
    )
  )
)
